# TTL640x480.net
KiCad netlist of a schematic drawn in EAGLE
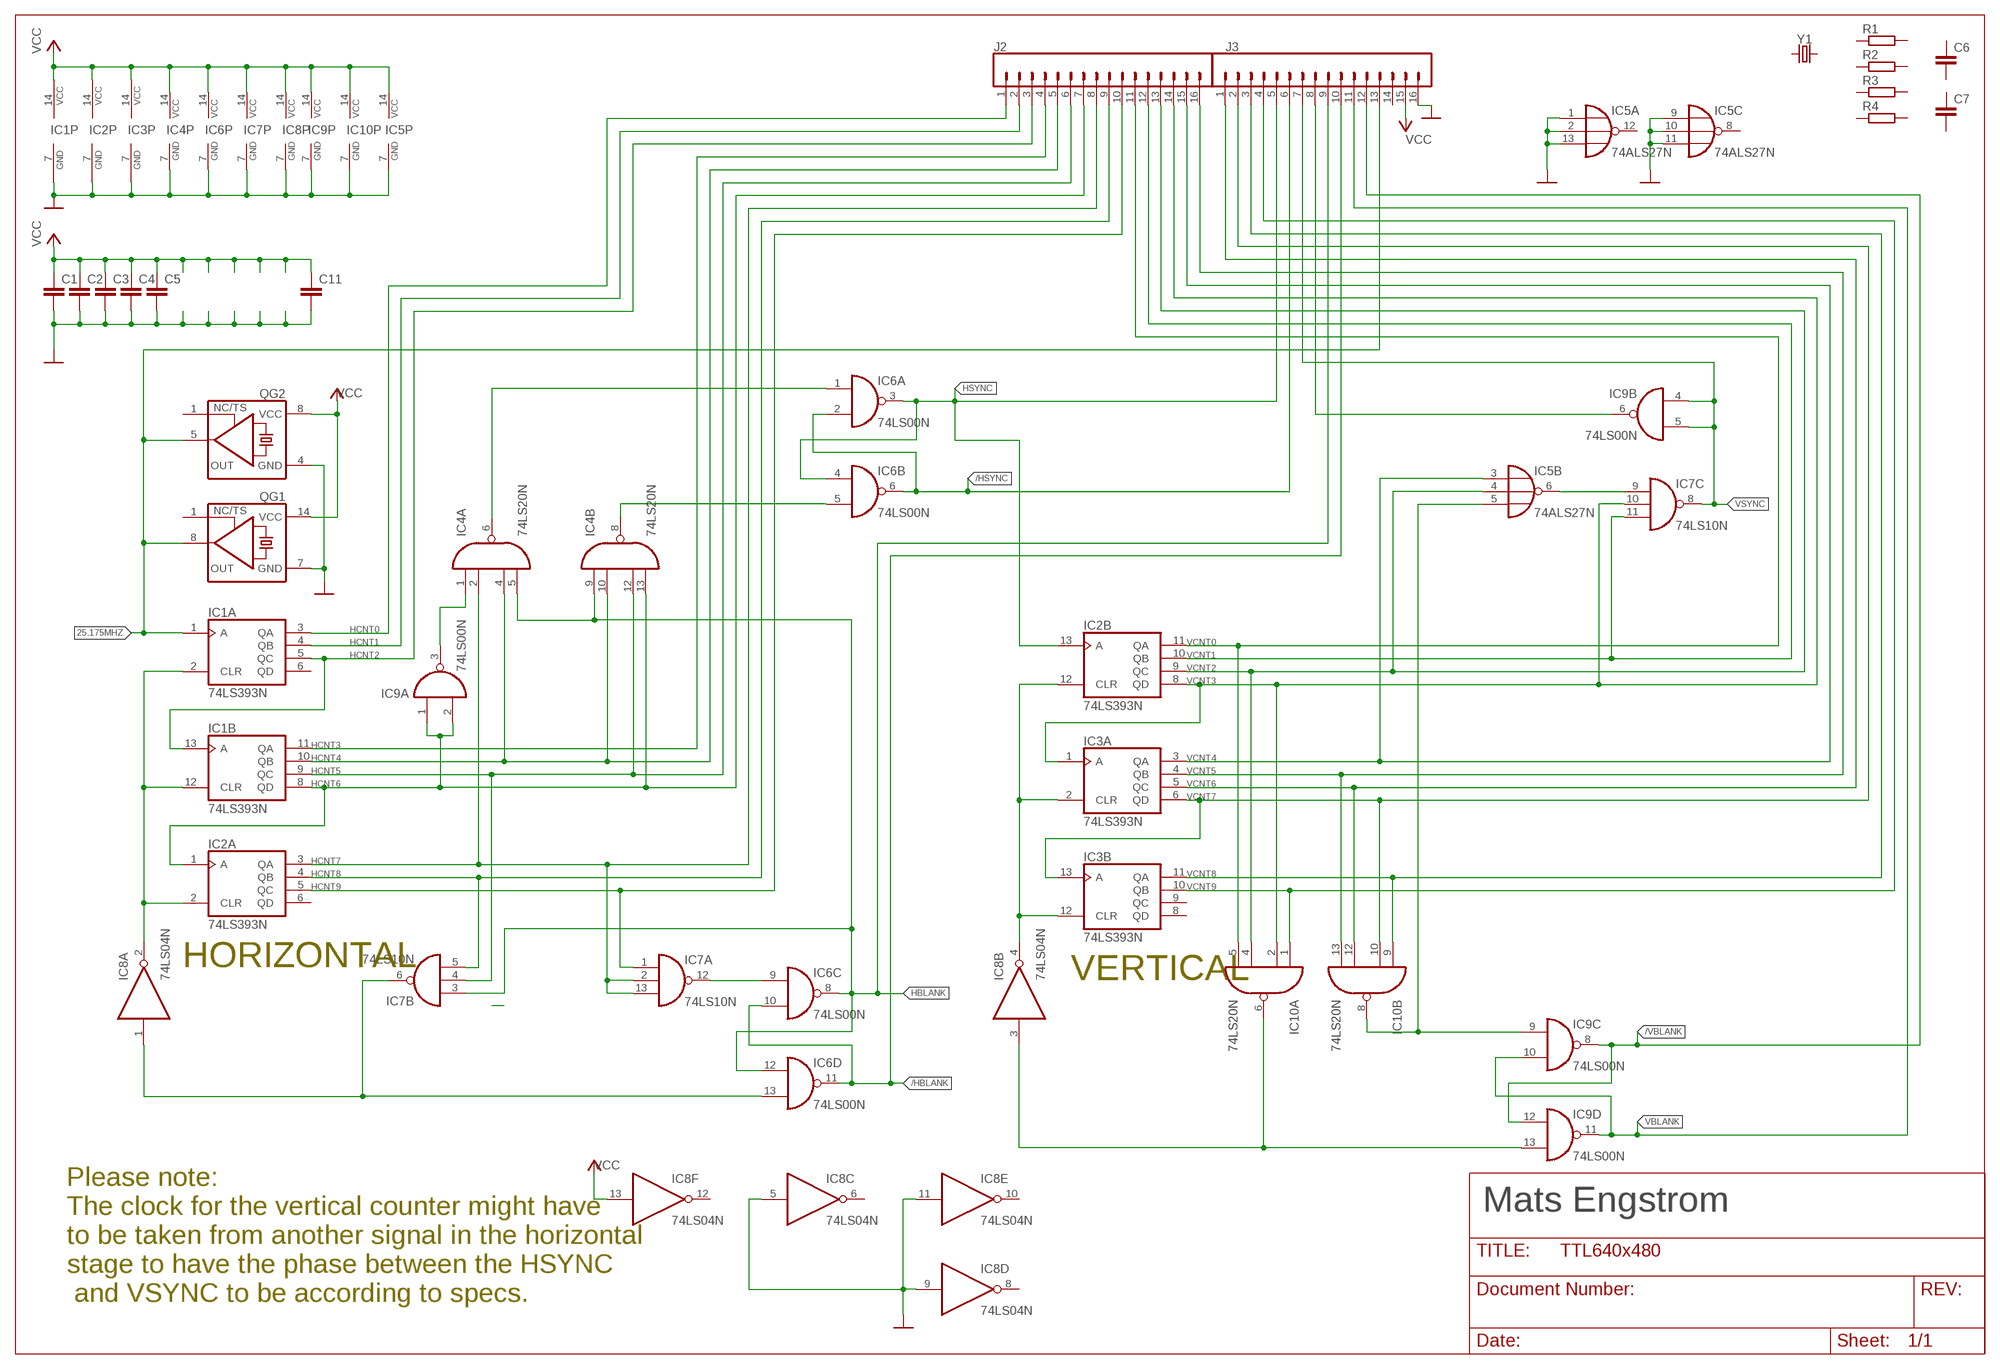
[diagram p0: schematic, sheet 1]

(export (version "E")
  (design (tool "Eeschema 10.0.6"))
  (components
    (comp (ref "C1")
      (value "C-EU050-024X044")
      (footprint "eagle-import:C050-024X044")
      (libsource (lib "eagle-import") (part "C-EU050-024X044"))
    )
    (comp (ref "C2")
      (value "C-EU050-024X044")
      (footprint "eagle-import:C050-024X044")
      (libsource (lib "eagle-import") (part "C-EU050-024X044"))
    )
    (comp (ref "C3")
      (value "C-EU050-024X044")
      (footprint "eagle-import:C050-024X044")
      (libsource (lib "eagle-import") (part "C-EU050-024X044"))
    )
    (comp (ref "C4")
      (value "C-EU050-024X044")
      (footprint "eagle-import:C050-024X044")
      (libsource (lib "eagle-import") (part "C-EU050-024X044"))
    )
    (comp (ref "C5")
      (value "C-EU050-024X044")
      (footprint "eagle-import:C050-024X044")
      (libsource (lib "eagle-import") (part "C-EU050-024X044"))
    )
    (comp (ref "C6")
      (value "C-EU050-024X044")
      (footprint "eagle-import:C050-024X044")
      (libsource (lib "eagle-import") (part "C-EU050-024X044"))
    )
    (comp (ref "C7")
      (value "C-EU050-024X044")
      (footprint "eagle-import:C050-024X044")
      (libsource (lib "eagle-import") (part "C-EU050-024X044"))
    )
    (comp (ref "C11")
      (value "C-EU050-024X044")
      (footprint "eagle-import:C050-024X044")
      (libsource (lib "eagle-import") (part "C-EU050-024X044"))
    )
    (comp (ref "IC1")
      (value "74LS393N")
      (footprint "eagle-import:DIL14")
      (libsource (lib "eagle-import") (part "74393NLS"))
    )
    (comp (ref "IC2")
      (value "74LS393N")
      (footprint "eagle-import:DIL14")
      (libsource (lib "eagle-import") (part "74393NLS"))
    )
    (comp (ref "IC3")
      (value "74LS393N")
      (footprint "eagle-import:DIL14")
      (libsource (lib "eagle-import") (part "74393NLS"))
    )
    (comp (ref "IC4")
      (value "74LS20N")
      (footprint "eagle-import:DIL14")
      (libsource (lib "eagle-import") (part "7420NLS"))
    )
    (comp (ref "IC5")
      (value "74ALS27N")
      (footprint "eagle-import:DIL14")
      (libsource (lib "eagle-import") (part "7427NALS"))
    )
    (comp (ref "IC6")
      (value "74LS00N")
      (footprint "eagle-import:DIL14")
      (libsource (lib "eagle-import") (part "7400NLS"))
    )
    (comp (ref "IC7")
      (value "74LS10N")
      (footprint "eagle-import:DIL14")
      (libsource (lib "eagle-import") (part "7410NLS"))
    )
    (comp (ref "IC8")
      (value "74LS04N")
      (footprint "eagle-import:DIL14")
      (libsource (lib "eagle-import") (part "7404NLS"))
    )
    (comp (ref "IC9")
      (value "74LS00N")
      (footprint "eagle-import:DIL14")
      (libsource (lib "eagle-import") (part "7400NLS"))
    )
    (comp (ref "IC10")
      (value "74LS20N")
      (footprint "eagle-import:DIL14")
      (libsource (lib "eagle-import") (part "7420NLS"))
    )
    (comp (ref "J2")
      (value "CONN_16")
      (footprint "eagle-import:1X16")
      (libsource (lib "eagle-import") (part "CONN_16"))
    )
    (comp (ref "J3")
      (value "CONN_16")
      (footprint "eagle-import:1X16")
      (libsource (lib "eagle-import") (part "CONN_16"))
    )
    (comp (ref "QG1")
      (value "XO-14")
      (footprint "eagle-import:DIL14S")
      (libsource (lib "eagle-import") (part "XO-14"))
    )
    (comp (ref "QG2")
      (value "XO-8")
      (footprint "eagle-import:DIL08S")
      (libsource (lib "eagle-import") (part "XO-8"))
    )
    (comp (ref "R1")
      (value "R-EU_0204/2V")
      (footprint "eagle-import:0204V")
      (libsource (lib "eagle-import") (part "R-EU_0204/2V"))
    )
    (comp (ref "R2")
      (value "R-EU_0204/2V")
      (footprint "eagle-import:0204V")
      (libsource (lib "eagle-import") (part "R-EU_0204/2V"))
    )
    (comp (ref "R3")
      (value "R-EU_0204/2V")
      (footprint "eagle-import:0204V")
      (libsource (lib "eagle-import") (part "R-EU_0204/2V"))
    )
    (comp (ref "R4")
      (value "R-EU_0204/2V")
      (footprint "eagle-import:0204V")
      (libsource (lib "eagle-import") (part "R-EU_0204/2V"))
    )
    (comp (ref "Y1")
      (value "CRYSTALPTH-HC49US")
      (footprint "eagle-import:HC49US")
      (libsource (lib "eagle-import") (part "CRYSTALPTH-HC49US"))
    )
  )
  (nets
    (net (code "1") (name "/HCNT0") (class "Default")
      (node (ref "IC1") (pin "3") (pinfunction "QA_3") (pintype "output"))
      (node (ref "J2") (pin "1") (pinfunction "1_1") (pintype "passive"))
    )
    (net (code "2") (name "/HCNT1") (class "Default")
      (node (ref "IC1") (pin "4") (pinfunction "QB_4") (pintype "output"))
      (node (ref "J2") (pin "2") (pinfunction "2_2") (pintype "passive"))
    )
    (net (code "3") (name "/HCNT2") (class "Default")
      (node (ref "IC1") (pin "13") (pinfunction "A_13") (pintype "input"))
      (node (ref "IC1") (pin "5") (pinfunction "QC_5") (pintype "output"))
      (node (ref "J2") (pin "3") (pinfunction "3_3") (pintype "passive"))
    )
    (net (code "4") (name "/HCNT3") (class "Default")
      (node (ref "IC1") (pin "11") (pinfunction "QA_11") (pintype "output"))
      (node (ref "J2") (pin "4") (pinfunction "4_4") (pintype "passive"))
    )
    (net (code "5") (name "/HCNT4") (class "Default")
      (node (ref "IC1") (pin "10") (pinfunction "QB_10") (pintype "output"))
      (node (ref "IC4") (pin "10") (pinfunction "I1_10") (pintype "input"))
      (node (ref "IC4") (pin "4") (pinfunction "I2_4") (pintype "input"))
      (node (ref "J2") (pin "5") (pinfunction "5_5") (pintype "passive"))
    )
    (net (code "6") (name "/HCNT5") (class "Default")
      (node (ref "IC1") (pin "9") (pinfunction "QC_9") (pintype "output"))
      (node (ref "IC4") (pin "12") (pinfunction "I2_12") (pintype "input"))
      (node (ref "IC7") (pin "4") (pinfunction "I1_4") (pintype "input"))
      (node (ref "J2") (pin "6") (pinfunction "6_6") (pintype "passive"))
    )
    (net (code "7") (name "/HCNT6") (class "Default")
      (node (ref "IC1") (pin "8") (pinfunction "QD_8") (pintype "output"))
      (node (ref "IC2") (pin "1") (pinfunction "A_1") (pintype "input"))
      (node (ref "IC4") (pin "13") (pinfunction "I3_13") (pintype "input"))
      (node (ref "IC9") (pin "1") (pinfunction "I0_1") (pintype "input"))
      (node (ref "IC9") (pin "2") (pinfunction "I1_2") (pintype "input"))
      (node (ref "J2") (pin "7") (pinfunction "7_7") (pintype "passive"))
    )
    (net (code "8") (name "/HCNT7") (class "Default")
      (node (ref "IC2") (pin "3") (pinfunction "QA_3") (pintype "output"))
      (node (ref "IC4") (pin "2") (pinfunction "I1_2") (pintype "input"))
      (node (ref "IC7") (pin "13") (pinfunction "I2_13") (pintype "input"))
      (node (ref "IC7") (pin "2") (pinfunction "I1_2") (pintype "input"))
      (node (ref "J2") (pin "8") (pinfunction "8_8") (pintype "passive"))
    )
    (net (code "9") (name "/HCNT8") (class "Default")
      (node (ref "IC2") (pin "4") (pinfunction "QB_4") (pintype "output"))
      (node (ref "IC7") (pin "5") (pinfunction "I2_5") (pintype "input"))
      (node (ref "J2") (pin "9") (pinfunction "9_9") (pintype "passive"))
    )
    (net (code "10") (name "/HCNT9") (class "Default")
      (node (ref "IC2") (pin "5") (pinfunction "QC_5") (pintype "output"))
      (node (ref "IC7") (pin "1") (pinfunction "I0_1") (pintype "input"))
      (node (ref "J2") (pin "10") (pinfunction "10_10") (pintype "passive"))
    )
    (net (code "11") (name "/VCNT0") (class "Default")
      (node (ref "IC10") (pin "5") (pinfunction "I3_5") (pintype "input"))
      (node (ref "IC2") (pin "11") (pinfunction "QA_11") (pintype "output"))
      (node (ref "J2") (pin "11") (pinfunction "11_11") (pintype "passive"))
    )
    (net (code "12") (name "/VCNT1") (class "Default")
      (node (ref "IC2") (pin "10") (pinfunction "QB_10") (pintype "output"))
      (node (ref "IC7") (pin "11") (pinfunction "I2_11") (pintype "input"))
      (node (ref "J2") (pin "12") (pinfunction "12_12") (pintype "passive"))
    )
    (net (code "13") (name "/VCNT2") (class "Default")
      (node (ref "IC10") (pin "4") (pinfunction "I2_4") (pintype "input"))
      (node (ref "IC2") (pin "9") (pinfunction "QC_9") (pintype "output"))
      (node (ref "IC5") (pin "4") (pinfunction "I1_4") (pintype "input"))
      (node (ref "J2") (pin "13") (pinfunction "13_13") (pintype "passive"))
    )
    (net (code "14") (name "/VCNT3") (class "Default")
      (node (ref "IC10") (pin "2") (pinfunction "I1_2") (pintype "input"))
      (node (ref "IC2") (pin "8") (pinfunction "QD_8") (pintype "output"))
      (node (ref "IC3") (pin "1") (pinfunction "A_1") (pintype "input"))
      (node (ref "IC7") (pin "10") (pinfunction "I1_10") (pintype "input"))
      (node (ref "J2") (pin "14") (pinfunction "14_14") (pintype "passive"))
    )
    (net (code "15") (name "/VCNT4") (class "Default")
      (node (ref "IC3") (pin "3") (pinfunction "QA_3") (pintype "output"))
      (node (ref "IC5") (pin "3") (pinfunction "I0_3") (pintype "input"))
      (node (ref "J2") (pin "15") (pinfunction "15_15") (pintype "passive"))
    )
    (net (code "16") (name "/VCNT5") (class "Default")
      (node (ref "IC10") (pin "13") (pinfunction "I3_13") (pintype "input"))
      (node (ref "IC3") (pin "4") (pinfunction "QB_4") (pintype "output"))
      (node (ref "J2") (pin "16") (pinfunction "16_16") (pintype "passive"))
    )
    (net (code "17") (name "/VCNT6") (class "Default")
      (node (ref "IC10") (pin "12") (pinfunction "I2_12") (pintype "input"))
      (node (ref "IC3") (pin "5") (pinfunction "QC_5") (pintype "output"))
      (node (ref "J3") (pin "1") (pinfunction "1_1") (pintype "passive"))
    )
    (net (code "18") (name "/VCNT7") (class "Default")
      (node (ref "IC10") (pin "10") (pinfunction "I1_10") (pintype "input"))
      (node (ref "IC3") (pin "13") (pinfunction "A_13") (pintype "input"))
      (node (ref "IC3") (pin "6") (pinfunction "QD_6") (pintype "output"))
      (node (ref "J3") (pin "2") (pinfunction "2_2") (pintype "passive"))
    )
    (net (code "19") (name "/VCNT8") (class "Default")
      (node (ref "IC10") (pin "9") (pinfunction "I0_9") (pintype "input"))
      (node (ref "IC3") (pin "11") (pinfunction "QA_11") (pintype "output"))
      (node (ref "J3") (pin "3") (pinfunction "3_3") (pintype "passive"))
    )
    (net (code "20") (name "/VCNT9") (class "Default")
      (node (ref "IC10") (pin "1") (pinfunction "I0_1") (pintype "input"))
      (node (ref "IC3") (pin "10") (pinfunction "QB_10") (pintype "output"))
      (node (ref "J3") (pin "4") (pinfunction "4_4") (pintype "passive"))
    )
    (net (code "21") (name "25.175MHZ") (class "Default")
      (node (ref "IC1") (pin "1") (pinfunction "A_1") (pintype "input"))
      (node (ref "J3") (pin "13") (pinfunction "13_13") (pintype "passive"))
      (node (ref "QG1") (pin "8") (pinfunction "OUT_8") (pintype "output"))
      (node (ref "QG2") (pin "5") (pinfunction "OUT_5") (pintype "output"))
    )
    (net (code "22") (name "GND") (class "Default")
      (node (ref "C1") (pin "2") (pinfunction "2_2") (pintype "passive"))
      (node (ref "C11") (pin "2") (pinfunction "2_2") (pintype "passive"))
      (node (ref "C2") (pin "2") (pinfunction "2_2") (pintype "passive"))
      (node (ref "C3") (pin "2") (pinfunction "2_2") (pintype "passive"))
      (node (ref "C4") (pin "2") (pinfunction "2_2") (pintype "passive"))
      (node (ref "C5") (pin "2") (pinfunction "2_2") (pintype "passive"))
      (node (ref "IC1") (pin "7") (pinfunction "GND_7") (pintype "power_in"))
      (node (ref "IC10") (pin "7") (pinfunction "GND_7") (pintype "power_in"))
      (node (ref "IC2") (pin "7") (pinfunction "GND_7") (pintype "power_in"))
      (node (ref "IC3") (pin "7") (pinfunction "GND_7") (pintype "power_in"))
      (node (ref "IC4") (pin "7") (pinfunction "GND_7") (pintype "power_in"))
      (node (ref "IC5") (pin "1") (pinfunction "I0_1") (pintype "input"))
      (node (ref "IC5") (pin "10") (pinfunction "I1_10") (pintype "input"))
      (node (ref "IC5") (pin "11") (pinfunction "I2_11") (pintype "input"))
      (node (ref "IC5") (pin "13") (pinfunction "I2_13") (pintype "input"))
      (node (ref "IC5") (pin "2") (pinfunction "I1_2") (pintype "input"))
      (node (ref "IC5") (pin "7") (pinfunction "GND_7") (pintype "power_in"))
      (node (ref "IC5") (pin "9") (pinfunction "I0_9") (pintype "input"))
      (node (ref "IC6") (pin "7") (pinfunction "GND_7") (pintype "power_in"))
      (node (ref "IC7") (pin "7") (pinfunction "GND_7") (pintype "power_in"))
      (node (ref "IC8") (pin "11") (pinfunction "I_11") (pintype "input"))
      (node (ref "IC8") (pin "5") (pinfunction "I_5") (pintype "input"))
      (node (ref "IC8") (pin "7") (pinfunction "GND_7") (pintype "power_in"))
      (node (ref "IC8") (pin "9") (pinfunction "I_9") (pintype "input"))
      (node (ref "IC9") (pin "7") (pinfunction "GND_7") (pintype "power_in"))
      (node (ref "J3") (pin "16") (pinfunction "16_16") (pintype "passive"))
      (node (ref "QG1") (pin "7") (pinfunction "GND_7") (pintype "power_in"))
      (node (ref "QG2") (pin "4") (pinfunction "GND_4") (pintype "power_in"))
    )
    (net (code "23") (name "HBLANK") (class "Default")
      (node (ref "IC4") (pin "5") (pinfunction "I3_5") (pintype "input"))
      (node (ref "IC4") (pin "9") (pinfunction "I0_9") (pintype "input"))
      (node (ref "IC6") (pin "12") (pinfunction "I0_12") (pintype "input"))
      (node (ref "IC6") (pin "8") (pinfunction "O_8") (pintype "output"))
      (node (ref "IC7") (pin "3") (pinfunction "I0_3") (pintype "input"))
      (node (ref "J3") (pin "9") (pinfunction "9_9") (pintype "passive"))
    )
    (net (code "24") (name "HSYNC") (class "Default")
      (node (ref "IC2") (pin "13") (pinfunction "A_13") (pintype "input"))
      (node (ref "IC6") (pin "3") (pinfunction "O_3") (pintype "output"))
      (node (ref "IC6") (pin "4") (pinfunction "I0_4") (pintype "input"))
      (node (ref "J3") (pin "5") (pinfunction "5_5") (pintype "passive"))
    )
    (net (code "25") (name "Net-(IC1A-CLR)") (class "Default")
      (node (ref "IC1") (pin "12") (pinfunction "CLR_12") (pintype "input"))
      (node (ref "IC1") (pin "2") (pinfunction "CLR_2") (pintype "input"))
      (node (ref "IC2") (pin "2") (pinfunction "CLR_2") (pintype "input"))
      (node (ref "IC8") (pin "2") (pinfunction "O_2") (pintype "output"))
    )
    (net (code "26") (name "Net-(IC2B-CLR)") (class "Default")
      (node (ref "IC2") (pin "12") (pinfunction "CLR_12") (pintype "input"))
      (node (ref "IC3") (pin "12") (pinfunction "CLR_12") (pintype "input"))
      (node (ref "IC3") (pin "2") (pinfunction "CLR_2") (pintype "input"))
      (node (ref "IC8") (pin "4") (pinfunction "O_4") (pintype "output"))
    )
    (net (code "27") (name "Net-(IC4A-I0)") (class "Default")
      (node (ref "IC4") (pin "1") (pinfunction "I0_1") (pintype "input"))
      (node (ref "IC9") (pin "3") (pinfunction "O_3") (pintype "output"))
    )
    (net (code "28") (name "Net-(IC4A-O)") (class "Default")
      (node (ref "IC4") (pin "6") (pinfunction "O_6") (pintype "output"))
      (node (ref "IC6") (pin "1") (pinfunction "I0_1") (pintype "input"))
    )
    (net (code "29") (name "Net-(IC4B-O)") (class "Default")
      (node (ref "IC4") (pin "8") (pinfunction "O_8") (pintype "output"))
      (node (ref "IC6") (pin "5") (pinfunction "I1_5") (pintype "input"))
    )
    (net (code "30") (name "Net-(IC5B-O)") (class "Default")
      (node (ref "IC5") (pin "6") (pinfunction "O_6") (pintype "output"))
      (node (ref "IC7") (pin "9") (pinfunction "I0_9") (pintype "input"))
    )
    (net (code "31") (name "Net-(IC6C-I0)") (class "Default")
      (node (ref "IC6") (pin "9") (pinfunction "I0_9") (pintype "input"))
      (node (ref "IC7") (pin "12") (pinfunction "O_12") (pintype "output"))
    )
    (net (code "32") (name "Net-(IC6D-I1)") (class "Default")
      (node (ref "IC6") (pin "13") (pinfunction "I1_13") (pintype "input"))
      (node (ref "IC7") (pin "6") (pinfunction "O_6") (pintype "output"))
      (node (ref "IC8") (pin "1") (pinfunction "I_1") (pintype "input"))
    )
    (net (code "33") (name "Net-(IC9B-O)") (class "Default")
      (node (ref "IC9") (pin "6") (pinfunction "O_6") (pintype "output"))
      (node (ref "J3") (pin "8") (pinfunction "8_8") (pintype "passive"))
    )
    (net (code "34") (name "Net-(IC10A-O)") (class "Default")
      (node (ref "IC10") (pin "6") (pinfunction "O_6") (pintype "output"))
      (node (ref "IC8") (pin "3") (pinfunction "I_3") (pintype "input"))
      (node (ref "IC9") (pin "13") (pinfunction "I1_13") (pintype "input"))
    )
    (net (code "35") (name "Net-(IC10B-O)") (class "Default")
      (node (ref "IC10") (pin "8") (pinfunction "O_8") (pintype "output"))
      (node (ref "IC5") (pin "5") (pinfunction "I2_5") (pintype "input"))
      (node (ref "IC9") (pin "9") (pinfunction "I0_9") (pintype "input"))
    )
    (net (code "36") (name "VBLANK") (class "Default")
      (node (ref "IC9") (pin "10") (pinfunction "I1_10") (pintype "input"))
      (node (ref "IC9") (pin "11") (pinfunction "O_11") (pintype "output"))
      (node (ref "J3") (pin "11") (pinfunction "11_11") (pintype "passive"))
    )
    (net (code "37") (name "VCC") (class "Default")
      (node (ref "C1") (pin "1") (pinfunction "1_1") (pintype "passive"))
      (node (ref "C11") (pin "1") (pinfunction "1_1") (pintype "passive"))
      (node (ref "C2") (pin "1") (pinfunction "1_1") (pintype "passive"))
      (node (ref "C3") (pin "1") (pinfunction "1_1") (pintype "passive"))
      (node (ref "C4") (pin "1") (pinfunction "1_1") (pintype "passive"))
      (node (ref "C5") (pin "1") (pinfunction "1_1") (pintype "passive"))
      (node (ref "IC1") (pin "14") (pinfunction "VCC_14") (pintype "power_in"))
      (node (ref "IC10") (pin "14") (pinfunction "VCC_14") (pintype "power_in"))
      (node (ref "IC2") (pin "14") (pinfunction "VCC_14") (pintype "power_in"))
      (node (ref "IC3") (pin "14") (pinfunction "VCC_14") (pintype "power_in"))
      (node (ref "IC4") (pin "14") (pinfunction "VCC_14") (pintype "power_in"))
      (node (ref "IC5") (pin "14") (pinfunction "VCC_14") (pintype "power_in"))
      (node (ref "IC6") (pin "14") (pinfunction "VCC_14") (pintype "power_in"))
      (node (ref "IC7") (pin "14") (pinfunction "VCC_14") (pintype "power_in"))
      (node (ref "IC8") (pin "13") (pinfunction "I_13") (pintype "input"))
      (node (ref "IC8") (pin "14") (pinfunction "VCC_14") (pintype "power_in"))
      (node (ref "IC9") (pin "14") (pinfunction "VCC_14") (pintype "power_in"))
      (node (ref "J3") (pin "15") (pinfunction "15_15") (pintype "passive"))
      (node (ref "QG1") (pin "14") (pinfunction "VCC_14") (pintype "power_in"))
      (node (ref "QG2") (pin "8") (pinfunction "VCC_8") (pintype "power_in"))
    )
    (net (code "38") (name "VSYNC") (class "Default")
      (node (ref "IC7") (pin "8") (pinfunction "O_8") (pintype "output"))
      (node (ref "IC9") (pin "4") (pinfunction "I0_4") (pintype "input"))
      (node (ref "IC9") (pin "5") (pinfunction "I1_5") (pintype "input"))
      (node (ref "J3") (pin "7") (pinfunction "7_7") (pintype "passive"))
    )
    (net (code "39") (name "unconnected-(C6-Pad1)") (class "Default")
      (node (ref "C6") (pin "1") (pinfunction "1_1") (pintype "passive"))
    )
    (net (code "40") (name "unconnected-(C6-Pad2)") (class "Default")
      (node (ref "C6") (pin "2") (pinfunction "2_2") (pintype "passive"))
    )
    (net (code "41") (name "unconnected-(C7-Pad1)") (class "Default")
      (node (ref "C7") (pin "1") (pinfunction "1_1") (pintype "passive"))
    )
    (net (code "42") (name "unconnected-(C7-Pad2)") (class "Default")
      (node (ref "C7") (pin "2") (pinfunction "2_2") (pintype "passive"))
    )
    (net (code "43") (name "unconnected-(IC1A-QD-Pad6)") (class "Default")
      (node (ref "IC1") (pin "6") (pinfunction "QD_6") (pintype "output"))
    )
    (net (code "44") (name "unconnected-(IC2A-QD-Pad6)") (class "Default")
      (node (ref "IC2") (pin "6") (pinfunction "QD_6") (pintype "output"))
    )
    (net (code "45") (name "unconnected-(IC3B-QC-Pad9)") (class "Default")
      (node (ref "IC3") (pin "9") (pinfunction "QC_9") (pintype "output"))
    )
    (net (code "46") (name "unconnected-(IC3B-QD-Pad8)") (class "Default")
      (node (ref "IC3") (pin "8") (pinfunction "QD_8") (pintype "output"))
    )
    (net (code "47") (name "unconnected-(IC5A-O-Pad12)") (class "Default")
      (node (ref "IC5") (pin "12") (pinfunction "O_12") (pintype "output"))
    )
    (net (code "48") (name "unconnected-(IC5C-O-Pad8)") (class "Default")
      (node (ref "IC5") (pin "8") (pinfunction "O_8") (pintype "output"))
    )
    (net (code "49") (name "unconnected-(IC8C-O-Pad6)") (class "Default")
      (node (ref "IC8") (pin "6") (pinfunction "O_6") (pintype "output"))
    )
    (net (code "50") (name "unconnected-(IC8D-O-Pad8)") (class "Default")
      (node (ref "IC8") (pin "8") (pinfunction "O_8") (pintype "output"))
    )
    (net (code "51") (name "unconnected-(IC8E-O-Pad10)") (class "Default")
      (node (ref "IC8") (pin "10") (pinfunction "O_10") (pintype "output"))
    )
    (net (code "52") (name "unconnected-(IC8F-O-Pad12)") (class "Default")
      (node (ref "IC8") (pin "12") (pinfunction "O_12") (pintype "output"))
    )
    (net (code "53") (name "unconnected-(J3-Pad14)") (class "Default")
      (node (ref "J3") (pin "14") (pinfunction "14_14") (pintype "passive"))
    )
    (net (code "54") (name "unconnected-(QG1-TS-Pad1)") (class "Default")
      (node (ref "QG1") (pin "1") (pinfunction "TS_1") (pintype "passive"))
    )
    (net (code "55") (name "unconnected-(QG2-TS-Pad1)") (class "Default")
      (node (ref "QG2") (pin "1") (pinfunction "TS_1") (pintype "passive"))
    )
    (net (code "56") (name "unconnected-(R1-Pad1)") (class "Default")
      (node (ref "R1") (pin "1") (pinfunction "1_1") (pintype "passive"))
    )
    (net (code "57") (name "unconnected-(R1-Pad2)") (class "Default")
      (node (ref "R1") (pin "2") (pinfunction "2_2") (pintype "passive"))
    )
    (net (code "58") (name "unconnected-(R2-Pad1)") (class "Default")
      (node (ref "R2") (pin "1") (pinfunction "1_1") (pintype "passive"))
    )
    (net (code "59") (name "unconnected-(R2-Pad2)") (class "Default")
      (node (ref "R2") (pin "2") (pinfunction "2_2") (pintype "passive"))
    )
    (net (code "60") (name "unconnected-(R3-Pad1)") (class "Default")
      (node (ref "R3") (pin "1") (pinfunction "1_1") (pintype "passive"))
    )
    (net (code "61") (name "unconnected-(R3-Pad2)") (class "Default")
      (node (ref "R3") (pin "2") (pinfunction "2_2") (pintype "passive"))
    )
    (net (code "62") (name "unconnected-(R4-Pad1)") (class "Default")
      (node (ref "R4") (pin "1") (pinfunction "1_1") (pintype "passive"))
    )
    (net (code "63") (name "unconnected-(R4-Pad2)") (class "Default")
      (node (ref "R4") (pin "2") (pinfunction "2_2") (pintype "passive"))
    )
    (net (code "64") (name "unconnected-(Y1-Pad1)") (class "Default")
      (node (ref "Y1") (pin "1") (pinfunction "1_1") (pintype "passive"))
    )
    (net (code "65") (name "unconnected-(Y1-Pad2)") (class "Default")
      (node (ref "Y1") (pin "2") (pinfunction "2_2") (pintype "passive"))
    )
    (net (code "66") (name "{slash}HBLANK") (class "Default")
      (node (ref "IC6") (pin "10") (pinfunction "I1_10") (pintype "input"))
      (node (ref "IC6") (pin "11") (pinfunction "O_11") (pintype "output"))
      (node (ref "J3") (pin "10") (pinfunction "10_10") (pintype "passive"))
    )
    (net (code "67") (name "{slash}HSYNC") (class "Default")
      (node (ref "IC6") (pin "2") (pinfunction "I1_2") (pintype "input"))
      (node (ref "IC6") (pin "6") (pinfunction "O_6") (pintype "output"))
      (node (ref "J3") (pin "6") (pinfunction "6_6") (pintype "passive"))
    )
    (net (code "68") (name "{slash}VBLANK") (class "Default")
      (node (ref "IC9") (pin "12") (pinfunction "I0_12") (pintype "input"))
      (node (ref "IC9") (pin "8") (pinfunction "O_8") (pintype "output"))
      (node (ref "J3") (pin "12") (pinfunction "12_12") (pintype "passive"))
    )
  )
)
